# Adaptor_Board.net
KiCad netlist of a schematic drawn in EAGLE
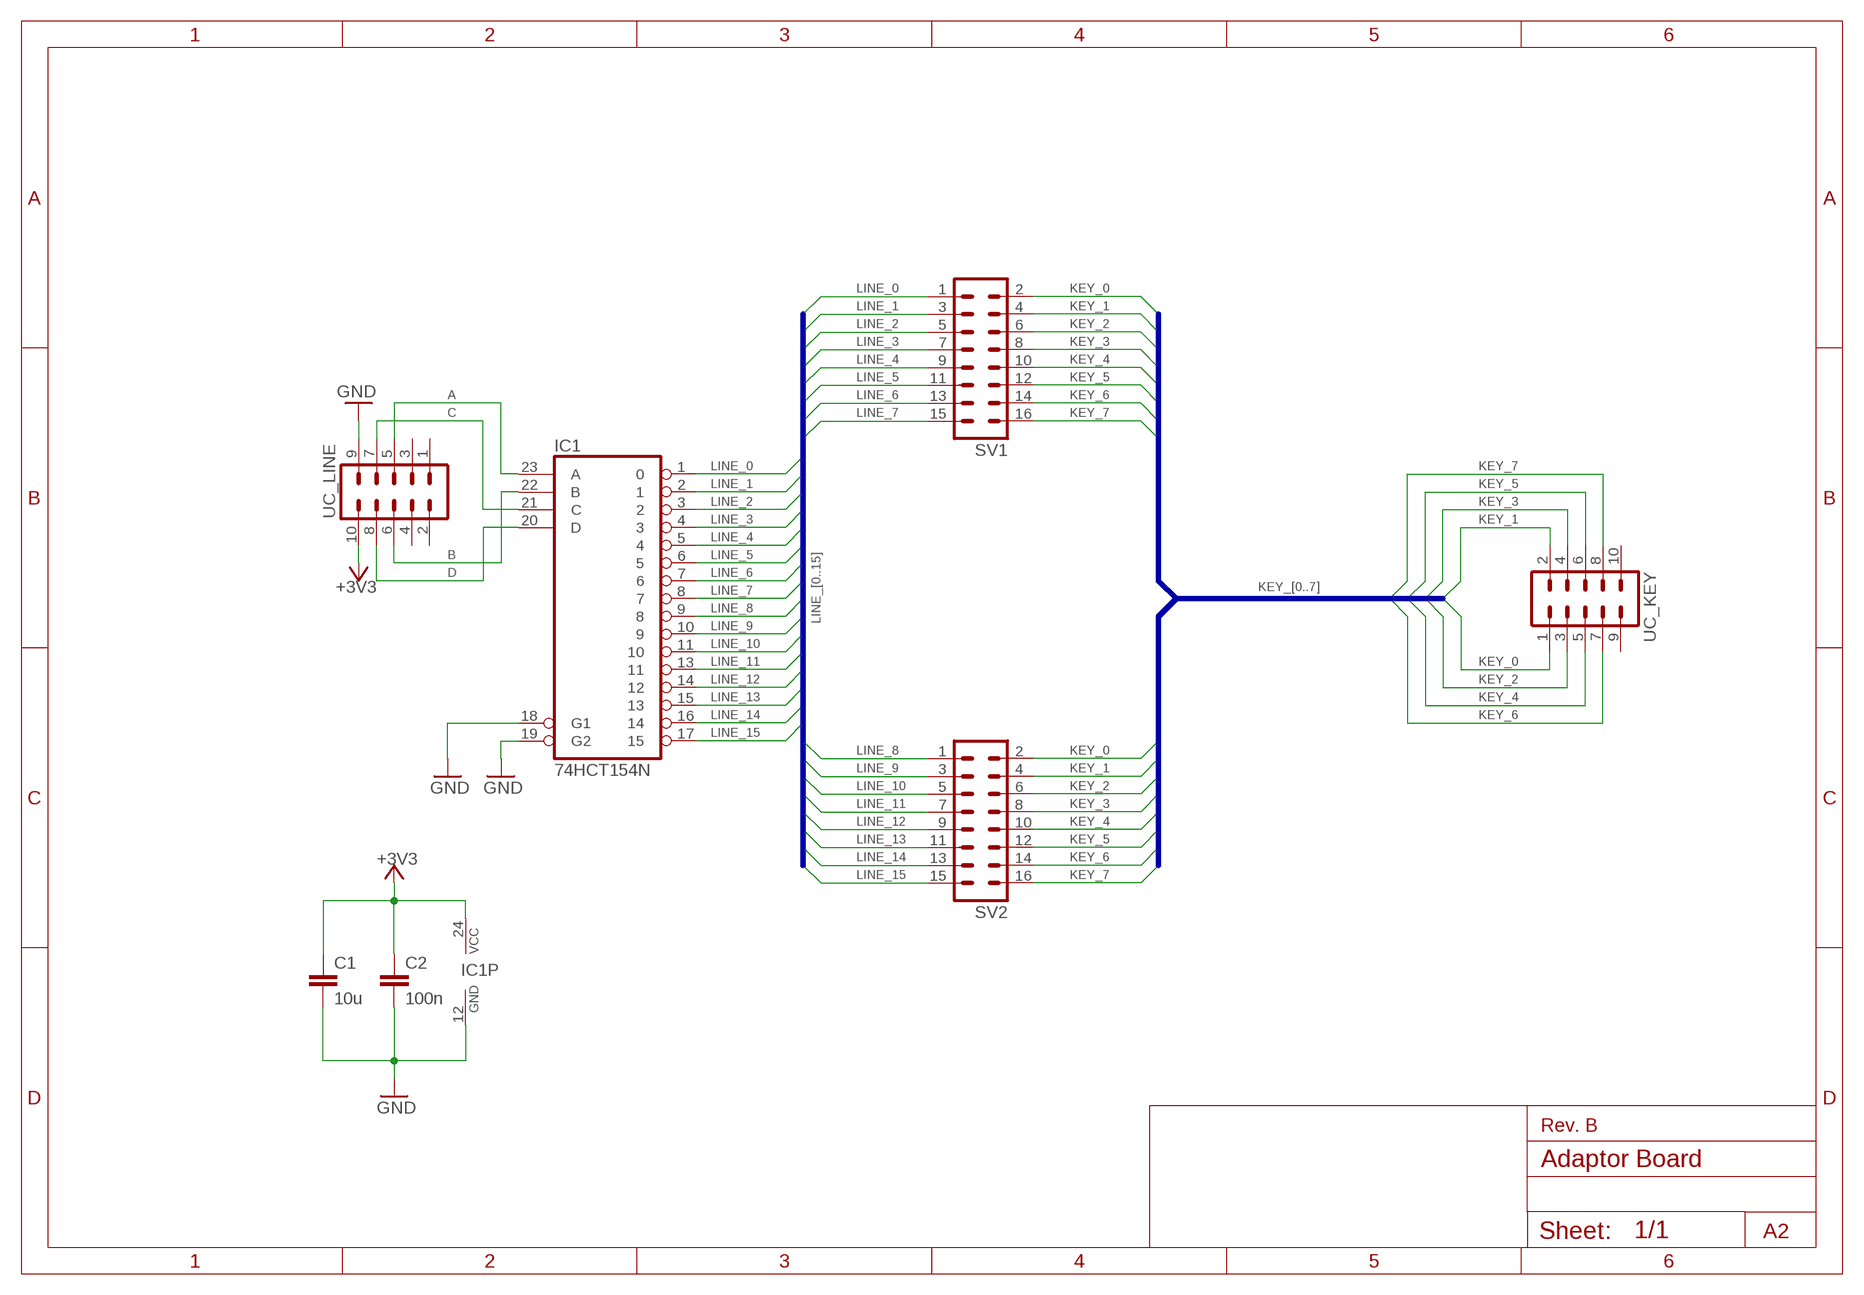
[diagram p0: schematic, sheet 1]

(export (version "E")
  (design (tool "Eeschema 10.0.6"))
  (components
    (comp (ref "C1")
      (value "10u")
      (footprint "eagle-import:C025-024X044")
      (libsource (lib "eagle-import") (part "C-EU025-024X044"))
    )
    (comp (ref "C2")
      (value "100n")
      (footprint "eagle-import:C025-024X044")
      (libsource (lib "eagle-import") (part "C-EU025-024X044"))
    )
    (comp (ref "IC1")
      (value "74HCT154N")
      (footprint "eagle-import:DIL24-6")
      (libsource (lib "eagle-import") (part "74154NHCT"))
    )
    (comp (ref "SV1")
      (value "ML16")
      (footprint "eagle-import:ML16")
      (libsource (lib "eagle-import") (part "ML16"))
    )
    (comp (ref "SV2")
      (value "ML16")
      (footprint "eagle-import:ML16")
      (libsource (lib "eagle-import") (part "ML16"))
    )
    (comp (ref "UC_KEY")
      (value "ML10")
      (footprint "eagle-import:ML10")
      (libsource (lib "eagle-import") (part "ML10"))
    )
    (comp (ref "UC_LINE")
      (value "ML10")
      (footprint "eagle-import:ML10")
      (libsource (lib "eagle-import") (part "ML10"))
    )
  )
  (nets
    (net (code "1") (name "+3V3") (class "Default")
      (node (ref "C1") (pin "1") (pinfunction "1_1") (pintype "passive"))
      (node (ref "C2") (pin "1") (pinfunction "1_1") (pintype "passive"))
      (node (ref "IC1") (pin "24") (pinfunction "VCC_24") (pintype "power_in"))
      (node (ref "UC_LINE") (pin "10") (pinfunction "10_10") (pintype "passive"))
    )
    (net (code "2") (name "/A") (class "Default")
      (node (ref "IC1") (pin "23") (pinfunction "A_23") (pintype "input"))
      (node (ref "UC_LINE") (pin "5") (pinfunction "5_5") (pintype "passive"))
    )
    (net (code "3") (name "/B") (class "Default")
      (node (ref "IC1") (pin "22") (pinfunction "B_22") (pintype "input"))
      (node (ref "UC_LINE") (pin "6") (pinfunction "6_6") (pintype "passive"))
    )
    (net (code "4") (name "/C") (class "Default")
      (node (ref "IC1") (pin "21") (pinfunction "C_21") (pintype "input"))
      (node (ref "UC_LINE") (pin "7") (pinfunction "7_7") (pintype "passive"))
    )
    (net (code "5") (name "/D") (class "Default")
      (node (ref "IC1") (pin "20") (pinfunction "D_20") (pintype "input"))
      (node (ref "UC_LINE") (pin "8") (pinfunction "8_8") (pintype "passive"))
    )
    (net (code "6") (name "/KEY_0") (class "Default")
      (node (ref "SV1") (pin "2") (pinfunction "2_2") (pintype "passive"))
      (node (ref "SV2") (pin "2") (pinfunction "2_2") (pintype "passive"))
      (node (ref "UC_KEY") (pin "1") (pinfunction "1_1") (pintype "passive"))
    )
    (net (code "7") (name "/KEY_1") (class "Default")
      (node (ref "SV1") (pin "4") (pinfunction "4_4") (pintype "passive"))
      (node (ref "SV2") (pin "4") (pinfunction "4_4") (pintype "passive"))
      (node (ref "UC_KEY") (pin "2") (pinfunction "2_2") (pintype "passive"))
    )
    (net (code "8") (name "/KEY_2") (class "Default")
      (node (ref "SV1") (pin "6") (pinfunction "6_6") (pintype "passive"))
      (node (ref "SV2") (pin "6") (pinfunction "6_6") (pintype "passive"))
      (node (ref "UC_KEY") (pin "3") (pinfunction "3_3") (pintype "passive"))
    )
    (net (code "9") (name "/KEY_3") (class "Default")
      (node (ref "SV1") (pin "8") (pinfunction "8_8") (pintype "passive"))
      (node (ref "SV2") (pin "8") (pinfunction "8_8") (pintype "passive"))
      (node (ref "UC_KEY") (pin "4") (pinfunction "4_4") (pintype "passive"))
    )
    (net (code "10") (name "/KEY_4") (class "Default")
      (node (ref "SV1") (pin "10") (pinfunction "10_10") (pintype "passive"))
      (node (ref "SV2") (pin "10") (pinfunction "10_10") (pintype "passive"))
      (node (ref "UC_KEY") (pin "5") (pinfunction "5_5") (pintype "passive"))
    )
    (net (code "11") (name "/KEY_5") (class "Default")
      (node (ref "SV1") (pin "12") (pinfunction "12_12") (pintype "passive"))
      (node (ref "SV2") (pin "12") (pinfunction "12_12") (pintype "passive"))
      (node (ref "UC_KEY") (pin "6") (pinfunction "6_6") (pintype "passive"))
    )
    (net (code "12") (name "/KEY_6") (class "Default")
      (node (ref "SV1") (pin "14") (pinfunction "14_14") (pintype "passive"))
      (node (ref "SV2") (pin "14") (pinfunction "14_14") (pintype "passive"))
      (node (ref "UC_KEY") (pin "7") (pinfunction "7_7") (pintype "passive"))
    )
    (net (code "13") (name "/KEY_7") (class "Default")
      (node (ref "SV1") (pin "16") (pinfunction "16_16") (pintype "passive"))
      (node (ref "SV2") (pin "16") (pinfunction "16_16") (pintype "passive"))
      (node (ref "UC_KEY") (pin "8") (pinfunction "8_8") (pintype "passive"))
    )
    (net (code "15") (name "/LINE_0") (class "Default")
      (node (ref "IC1") (pin "1") (pinfunction "0_1") (pintype "output"))
      (node (ref "SV1") (pin "1") (pinfunction "1_1") (pintype "passive"))
    )
    (net (code "16") (name "/LINE_1") (class "Default")
      (node (ref "IC1") (pin "2") (pinfunction "1_2") (pintype "output"))
      (node (ref "SV1") (pin "3") (pinfunction "3_3") (pintype "passive"))
    )
    (net (code "17") (name "/LINE_2") (class "Default")
      (node (ref "IC1") (pin "3") (pinfunction "2_3") (pintype "output"))
      (node (ref "SV1") (pin "5") (pinfunction "5_5") (pintype "passive"))
    )
    (net (code "18") (name "/LINE_3") (class "Default")
      (node (ref "IC1") (pin "4") (pinfunction "3_4") (pintype "output"))
      (node (ref "SV1") (pin "7") (pinfunction "7_7") (pintype "passive"))
    )
    (net (code "19") (name "/LINE_4") (class "Default")
      (node (ref "IC1") (pin "5") (pinfunction "4_5") (pintype "output"))
      (node (ref "SV1") (pin "9") (pinfunction "9_9") (pintype "passive"))
    )
    (net (code "20") (name "/LINE_5") (class "Default")
      (node (ref "IC1") (pin "6") (pinfunction "5_6") (pintype "output"))
      (node (ref "SV1") (pin "11") (pinfunction "11_11") (pintype "passive"))
    )
    (net (code "21") (name "/LINE_6") (class "Default")
      (node (ref "IC1") (pin "7") (pinfunction "6_7") (pintype "output"))
      (node (ref "SV1") (pin "13") (pinfunction "13_13") (pintype "passive"))
    )
    (net (code "22") (name "/LINE_7") (class "Default")
      (node (ref "IC1") (pin "8") (pinfunction "7_8") (pintype "output"))
      (node (ref "SV1") (pin "15") (pinfunction "15_15") (pintype "passive"))
    )
    (net (code "23") (name "/LINE_8") (class "Default")
      (node (ref "IC1") (pin "9") (pinfunction "8_9") (pintype "output"))
      (node (ref "SV2") (pin "1") (pinfunction "1_1") (pintype "passive"))
    )
    (net (code "24") (name "/LINE_9") (class "Default")
      (node (ref "IC1") (pin "10") (pinfunction "9_10") (pintype "output"))
      (node (ref "SV2") (pin "3") (pinfunction "3_3") (pintype "passive"))
    )
    (net (code "25") (name "/LINE_10") (class "Default")
      (node (ref "IC1") (pin "11") (pinfunction "10_11") (pintype "output"))
      (node (ref "SV2") (pin "5") (pinfunction "5_5") (pintype "passive"))
    )
    (net (code "26") (name "/LINE_11") (class "Default")
      (node (ref "IC1") (pin "13") (pinfunction "11_13") (pintype "output"))
      (node (ref "SV2") (pin "7") (pinfunction "7_7") (pintype "passive"))
    )
    (net (code "27") (name "/LINE_12") (class "Default")
      (node (ref "IC1") (pin "14") (pinfunction "12_14") (pintype "output"))
      (node (ref "SV2") (pin "9") (pinfunction "9_9") (pintype "passive"))
    )
    (net (code "28") (name "/LINE_13") (class "Default")
      (node (ref "IC1") (pin "15") (pinfunction "13_15") (pintype "output"))
      (node (ref "SV2") (pin "11") (pinfunction "11_11") (pintype "passive"))
    )
    (net (code "29") (name "/LINE_14") (class "Default")
      (node (ref "IC1") (pin "16") (pinfunction "14_16") (pintype "output"))
      (node (ref "SV2") (pin "13") (pinfunction "13_13") (pintype "passive"))
    )
    (net (code "30") (name "/LINE_15") (class "Default")
      (node (ref "IC1") (pin "17") (pinfunction "15_17") (pintype "output"))
      (node (ref "SV2") (pin "15") (pinfunction "15_15") (pintype "passive"))
    )
    (net (code "32") (name "GND") (class "Default")
      (node (ref "C1") (pin "2") (pinfunction "2_2") (pintype "passive"))
      (node (ref "C2") (pin "2") (pinfunction "2_2") (pintype "passive"))
      (node (ref "IC1") (pin "12") (pinfunction "GND_12") (pintype "power_in"))
      (node (ref "IC1") (pin "18") (pinfunction "G1_18") (pintype "input"))
      (node (ref "IC1") (pin "19") (pinfunction "G2_19") (pintype "input"))
      (node (ref "UC_LINE") (pin "9") (pinfunction "9_9") (pintype "passive"))
    )
    (net (code "33") (name "unconnected-(UC_KEY-Pad9)") (class "Default")
      (node (ref "UC_KEY") (pin "9") (pinfunction "9_9") (pintype "passive"))
    )
    (net (code "34") (name "unconnected-(UC_KEY-Pad10)") (class "Default")
      (node (ref "UC_KEY") (pin "10") (pinfunction "10_10") (pintype "passive"))
    )
    (net (code "35") (name "unconnected-(UC_LINE-Pad1)") (class "Default")
      (node (ref "UC_LINE") (pin "1") (pinfunction "1_1") (pintype "passive"))
    )
    (net (code "36") (name "unconnected-(UC_LINE-Pad2)") (class "Default")
      (node (ref "UC_LINE") (pin "2") (pinfunction "2_2") (pintype "passive"))
    )
    (net (code "37") (name "unconnected-(UC_LINE-Pad3)") (class "Default")
      (node (ref "UC_LINE") (pin "3") (pinfunction "3_3") (pintype "passive"))
    )
    (net (code "38") (name "unconnected-(UC_LINE-Pad4)") (class "Default")
      (node (ref "UC_LINE") (pin "4") (pinfunction "4_4") (pintype "passive"))
    )
  )
)
